# PuenteHayEsquematico.net
KiCad netlist of a schematic drawn in Altium Designer
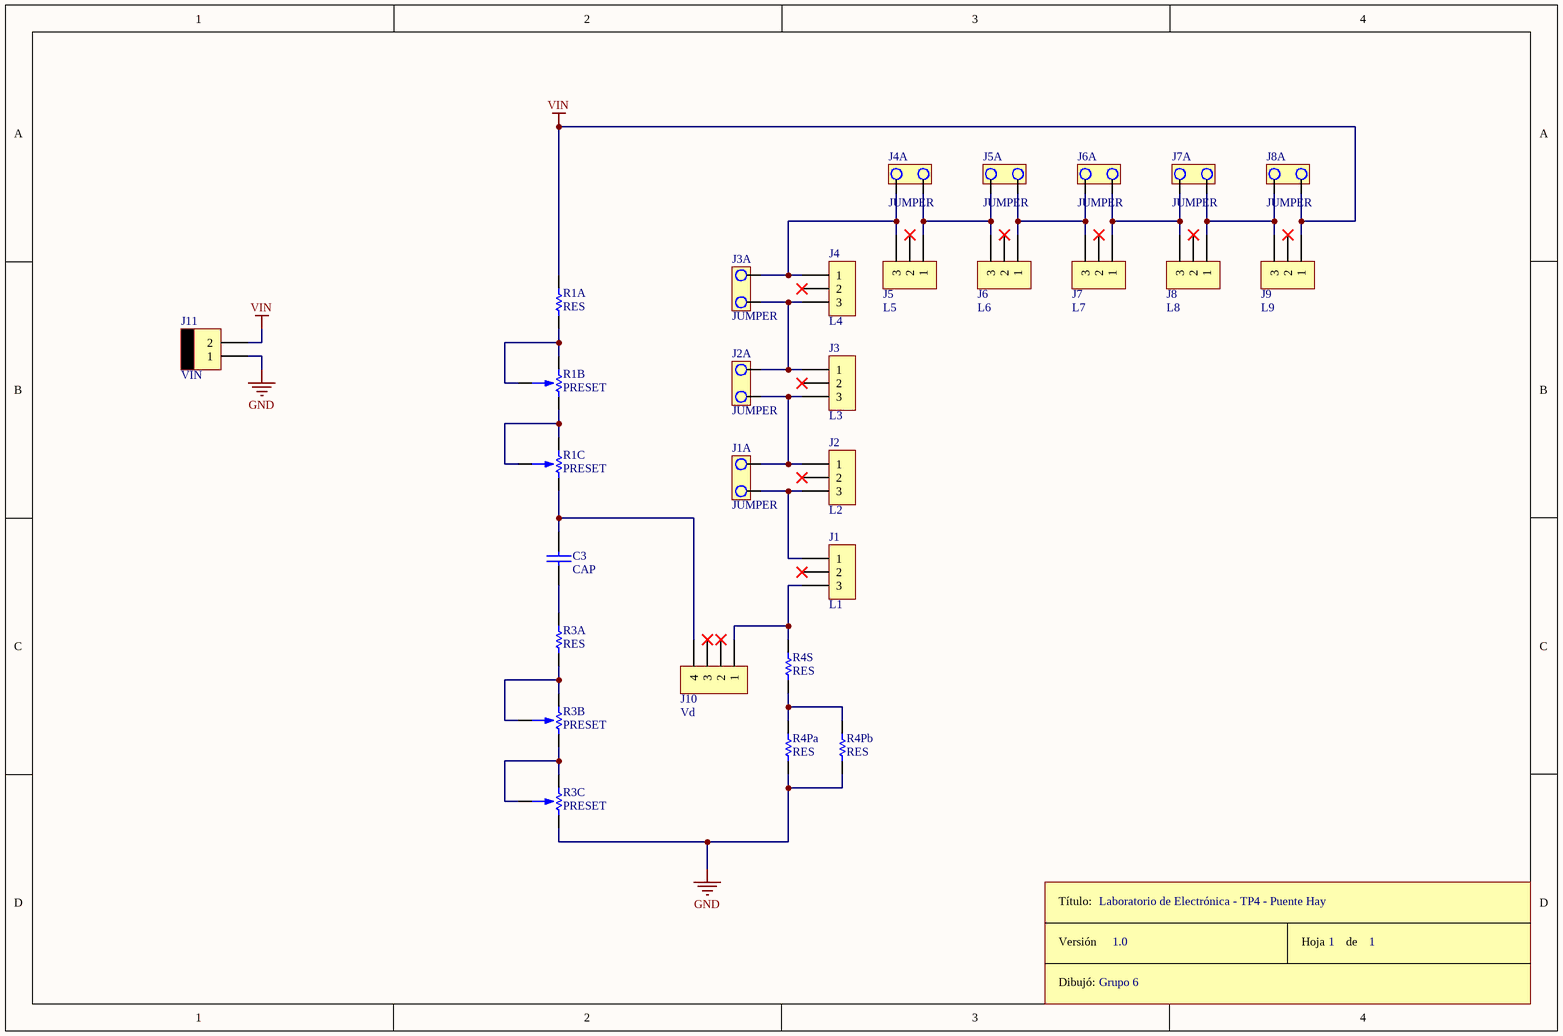
[diagram p0: PuenteHayEsquematico.SchDoc]

(export (version "E")
  (design (tool "Eeschema 10.0.6"))
  (components
    (comp (ref "C3") (value "CAP") (footprint "CAP200") (libsource (lib "LIBEBAL") (part "CAP")))
    (comp (ref "J1") (value "L1") (footprint "SIP3") (libsource (lib "LIBEBAL") (part "CON3")))
    (comp (ref "J1A") (value "JUMPER") (footprint "JUMPER2") (libsource (lib "LIBEBAL") (part "JUMPER")))
    (comp (ref "J2") (value "L2") (footprint "SIP3") (libsource (lib "LIBEBAL") (part "CON3")))
    (comp (ref "J2A") (value "JUMPER") (footprint "JUMPER2") (libsource (lib "LIBEBAL") (part "JUMPER")))
    (comp (ref "J3") (value "L3") (footprint "SIP3") (libsource (lib "LIBEBAL") (part "CON3")))
    (comp (ref "J3A") (value "JUMPER") (footprint "JUMPER2") (libsource (lib "LIBEBAL") (part "JUMPER")))
    (comp (ref "J4") (value "L4") (footprint "SIP3") (libsource (lib "LIBEBAL") (part "CON3")))
    (comp (ref "J4A") (value "JUMPER") (footprint "JUMPER2") (libsource (lib "") (part "JUMPER_1")))
    (comp (ref "J5") (value "L5") (footprint "SIP3") (libsource (lib "") (part "CON3_1")))
    (comp (ref "J5A") (value "JUMPER") (footprint "JUMPER2") (libsource (lib "") (part "JUMPER_1")))
    (comp (ref "J6") (value "L6") (footprint "SIP3") (libsource (lib "") (part "CON3_1")))
    (comp (ref "J6A") (value "JUMPER") (footprint "JUMPER2") (libsource (lib "") (part "JUMPER_1")))
    (comp (ref "J7") (value "L7") (footprint "SIP3") (libsource (lib "") (part "CON3_1")))
    (comp (ref "J7A") (value "JUMPER") (footprint "JUMPER2") (libsource (lib "") (part "JUMPER_1")))
    (comp (ref "J8") (value "L8") (footprint "SIP3") (libsource (lib "") (part "CON3_1")))
    (comp (ref "J8A") (value "JUMPER") (footprint "JUMPER2") (libsource (lib "") (part "JUMPER_1")))
    (comp (ref "J9") (value "L9") (footprint "SIP3") (libsource (lib "") (part "CON3_1")))
    (comp (ref "J10") (value "Vd") (footprint "SIP4") (libsource (lib "LIBEBAL") (part "CON4")))
    (comp (ref "J11") (value "VIN") (footprint "MOLEX2") (libsource (lib "LIBEBAL") (part "MOLEX2")))
    (comp (ref "R1A") (value "RES") (footprint "RES300") (libsource (lib "LIBEBAL") (part "RES")))
    (comp (ref "R1B") (value "PRESET") (footprint "PRESET V") (libsource (lib "LIBEBAL") (part "PRESET")))
    (comp (ref "R1C") (value "PRESET") (footprint "PRESET V") (libsource (lib "LIBEBAL") (part "PRESET")))
    (comp (ref "R3A") (value "RES") (footprint "RES300") (libsource (lib "LIBEBAL") (part "RES")))
    (comp (ref "R3B") (value "PRESET") (footprint "PRESET V") (libsource (lib "LIBEBAL") (part "PRESET")))
    (comp (ref "R3C") (value "PRESET") (footprint "PRESET V") (libsource (lib "LIBEBAL") (part "PRESET")))
    (comp (ref "R4Pa") (value "RES") (footprint "RES300") (libsource (lib "LIBEBAL") (part "RES")))
    (comp (ref "R4Pb") (value "RES") (footprint "RES300") (libsource (lib "LIBEBAL") (part "RES")))
    (comp (ref "R4S") (value "RES") (footprint "RES300") (libsource (lib "LIBEBAL") (part "RES")))
    (comp (ref "ROT1") (value "Rótulo") (libsource (lib "LIB PIO IX") (part "Rótulo")))
  )
  (nets
    (net (code "1") (name "GND") (class "Default")
      (node (ref "J11") (pin "1") (pinfunction "1_1") (pintype "passive"))
      (node (ref "R3C") (pin "1") (pinfunction "1_1") (pintype "passive"))
      (node (ref "R4Pa") (pin "1") (pinfunction "1_1") (pintype "passive"))
      (node (ref "R4Pb") (pin "1") (pinfunction "1_1") (pintype "passive"))
    )
    (net (code "2") (name "Net-(C3-Pad1)") (class "Default")
      (node (ref "C3") (pin "1") (pinfunction "1_1") (pintype "passive"))
      (node (ref "J10") (pin "4") (pinfunction "4_4") (pintype "passive"))
      (node (ref "R1C") (pin "1") (pinfunction "1_1") (pintype "passive"))
    )
    (net (code "3") (name "Net-(C3-Pad2)") (class "Default")
      (node (ref "C3") (pin "2") (pinfunction "2_2") (pintype "passive"))
      (node (ref "R3A") (pin "2") (pinfunction "2_2") (pintype "passive"))
    )
    (net (code "4") (name "Net-(J1-Pad1)") (class "Default")
      (node (ref "J1") (pin "1") (pinfunction "1_1") (pintype "passive"))
      (node (ref "J1A") (pin "2") (pinfunction "2_2") (pintype "passive"))
      (node (ref "J2") (pin "3") (pinfunction "3_3") (pintype "passive"))
    )
    (net (code "5") (name "Net-(J1-Pad3)") (class "Default")
      (node (ref "J1") (pin "3") (pinfunction "3_3") (pintype "passive"))
      (node (ref "J10") (pin "1") (pinfunction "1_1") (pintype "passive"))
      (node (ref "R4S") (pin "2") (pinfunction "2_2") (pintype "passive"))
    )
    (net (code "6") (name "Net-(J1A-Pad1)") (class "Default")
      (node (ref "J1A") (pin "1") (pinfunction "1_1") (pintype "passive"))
      (node (ref "J2") (pin "1") (pinfunction "1_1") (pintype "passive"))
      (node (ref "J2A") (pin "2") (pinfunction "2_2") (pintype "passive"))
      (node (ref "J3") (pin "3") (pinfunction "3_3") (pintype "passive"))
    )
    (net (code "7") (name "Net-(J2A-Pad1)") (class "Default")
      (node (ref "J2A") (pin "1") (pinfunction "1_1") (pintype "passive"))
      (node (ref "J3") (pin "1") (pinfunction "1_1") (pintype "passive"))
      (node (ref "J3A") (pin "2") (pinfunction "2_2") (pintype "passive"))
      (node (ref "J4") (pin "3") (pinfunction "3_3") (pintype "passive"))
    )
    (net (code "8") (name "Net-(J3A-Pad1)") (class "Default")
      (node (ref "J3A") (pin "1") (pinfunction "1_1") (pintype "passive"))
      (node (ref "J4") (pin "1") (pinfunction "1_1") (pintype "passive"))
      (node (ref "J4A") (pin "2") (pinfunction "2_2") (pintype "passive"))
      (node (ref "J5") (pin "3") (pinfunction "3_3") (pintype "passive"))
    )
    (net (code "9") (name "Net-(J4A-Pad1)") (class "Default")
      (node (ref "J4A") (pin "1") (pinfunction "1_1") (pintype "passive"))
      (node (ref "J5") (pin "1") (pinfunction "1_1") (pintype "passive"))
      (node (ref "J5A") (pin "2") (pinfunction "2_2") (pintype "passive"))
      (node (ref "J6") (pin "3") (pinfunction "3_3") (pintype "passive"))
    )
    (net (code "10") (name "Net-(J5A-Pad1)") (class "Default")
      (node (ref "J5A") (pin "1") (pinfunction "1_1") (pintype "passive"))
      (node (ref "J6") (pin "1") (pinfunction "1_1") (pintype "passive"))
      (node (ref "J6A") (pin "2") (pinfunction "2_2") (pintype "passive"))
      (node (ref "J7") (pin "3") (pinfunction "3_3") (pintype "passive"))
    )
    (net (code "11") (name "Net-(J6A-Pad1)") (class "Default")
      (node (ref "J6A") (pin "1") (pinfunction "1_1") (pintype "passive"))
      (node (ref "J7") (pin "1") (pinfunction "1_1") (pintype "passive"))
      (node (ref "J7A") (pin "2") (pinfunction "2_2") (pintype "passive"))
      (node (ref "J8") (pin "3") (pinfunction "3_3") (pintype "passive"))
    )
    (net (code "12") (name "Net-(J7A-Pad1)") (class "Default")
      (node (ref "J7A") (pin "1") (pinfunction "1_1") (pintype "passive"))
      (node (ref "J8") (pin "1") (pinfunction "1_1") (pintype "passive"))
      (node (ref "J8A") (pin "2") (pinfunction "2_2") (pintype "passive"))
      (node (ref "J9") (pin "3") (pinfunction "3_3") (pintype "passive"))
    )
    (net (code "13") (name "Net-(R1A-Pad1)") (class "Default")
      (node (ref "R1A") (pin "1") (pinfunction "1_1") (pintype "passive"))
      (node (ref "R1B") (pin "2") (pinfunction "2_2") (pintype "passive"))
      (node (ref "R1B") (pin "3") (pinfunction "3_3") (pintype "passive"))
    )
    (net (code "14") (name "Net-(R1B-Pad1)") (class "Default")
      (node (ref "R1B") (pin "1") (pinfunction "1_1") (pintype "passive"))
      (node (ref "R1C") (pin "2") (pinfunction "2_2") (pintype "passive"))
      (node (ref "R1C") (pin "3") (pinfunction "3_3") (pintype "passive"))
    )
    (net (code "15") (name "Net-(R3A-Pad1)") (class "Default")
      (node (ref "R3A") (pin "1") (pinfunction "1_1") (pintype "passive"))
      (node (ref "R3B") (pin "2") (pinfunction "2_2") (pintype "passive"))
      (node (ref "R3B") (pin "3") (pinfunction "3_3") (pintype "passive"))
    )
    (net (code "16") (name "Net-(R3B-Pad1)") (class "Default")
      (node (ref "R3B") (pin "1") (pinfunction "1_1") (pintype "passive"))
      (node (ref "R3C") (pin "2") (pinfunction "2_2") (pintype "passive"))
      (node (ref "R3C") (pin "3") (pinfunction "3_3") (pintype "passive"))
    )
    (net (code "17") (name "Net-(R4Pa-Pad2)") (class "Default")
      (node (ref "R4Pa") (pin "2") (pinfunction "2_2") (pintype "passive"))
      (node (ref "R4Pb") (pin "2") (pinfunction "2_2") (pintype "passive"))
      (node (ref "R4S") (pin "1") (pinfunction "1_1") (pintype "passive"))
    )
    (net (code "18") (name "VIN") (class "Default")
      (node (ref "J11") (pin "2") (pinfunction "2_2") (pintype "passive"))
      (node (ref "J8A") (pin "1") (pinfunction "1_1") (pintype "passive"))
      (node (ref "J9") (pin "1") (pinfunction "1_1") (pintype "passive"))
      (node (ref "R1A") (pin "2") (pinfunction "2_2") (pintype "passive"))
    )
    (net (code "19") (name "unconnected-(J1-Pad2)") (class "Default")
      (node (ref "J1") (pin "2") (pinfunction "2_2") (pintype "passive+no_connect"))
    )
    (net (code "20") (name "unconnected-(J2-Pad2)") (class "Default")
      (node (ref "J2") (pin "2") (pinfunction "2_2") (pintype "passive+no_connect"))
    )
    (net (code "21") (name "unconnected-(J3-Pad2)") (class "Default")
      (node (ref "J3") (pin "2") (pinfunction "2_2") (pintype "passive+no_connect"))
    )
    (net (code "22") (name "unconnected-(J4-Pad2)") (class "Default")
      (node (ref "J4") (pin "2") (pinfunction "2_2") (pintype "passive+no_connect"))
    )
    (net (code "23") (name "unconnected-(J5-Pad2)") (class "Default")
      (node (ref "J5") (pin "2") (pinfunction "2_2") (pintype "passive+no_connect"))
    )
    (net (code "24") (name "unconnected-(J6-Pad2)") (class "Default")
      (node (ref "J6") (pin "2") (pinfunction "2_2") (pintype "passive+no_connect"))
    )
    (net (code "25") (name "unconnected-(J7-Pad2)") (class "Default")
      (node (ref "J7") (pin "2") (pinfunction "2_2") (pintype "passive+no_connect"))
    )
    (net (code "26") (name "unconnected-(J8-Pad2)") (class "Default")
      (node (ref "J8") (pin "2") (pinfunction "2_2") (pintype "passive+no_connect"))
    )
    (net (code "27") (name "unconnected-(J9-Pad2)") (class "Default")
      (node (ref "J9") (pin "2") (pinfunction "2_2") (pintype "passive+no_connect"))
    )
    (net (code "28") (name "unconnected-(J10-Pad2)") (class "Default")
      (node (ref "J10") (pin "2") (pinfunction "2_2") (pintype "passive+no_connect"))
    )
    (net (code "29") (name "unconnected-(J10-Pad3)") (class "Default")
      (node (ref "J10") (pin "3") (pinfunction "3_3") (pintype "passive+no_connect"))
    )
  )
)
